# MCU_144_IOs.net
KiCad netlist of a schematic drawn in Altium Designer
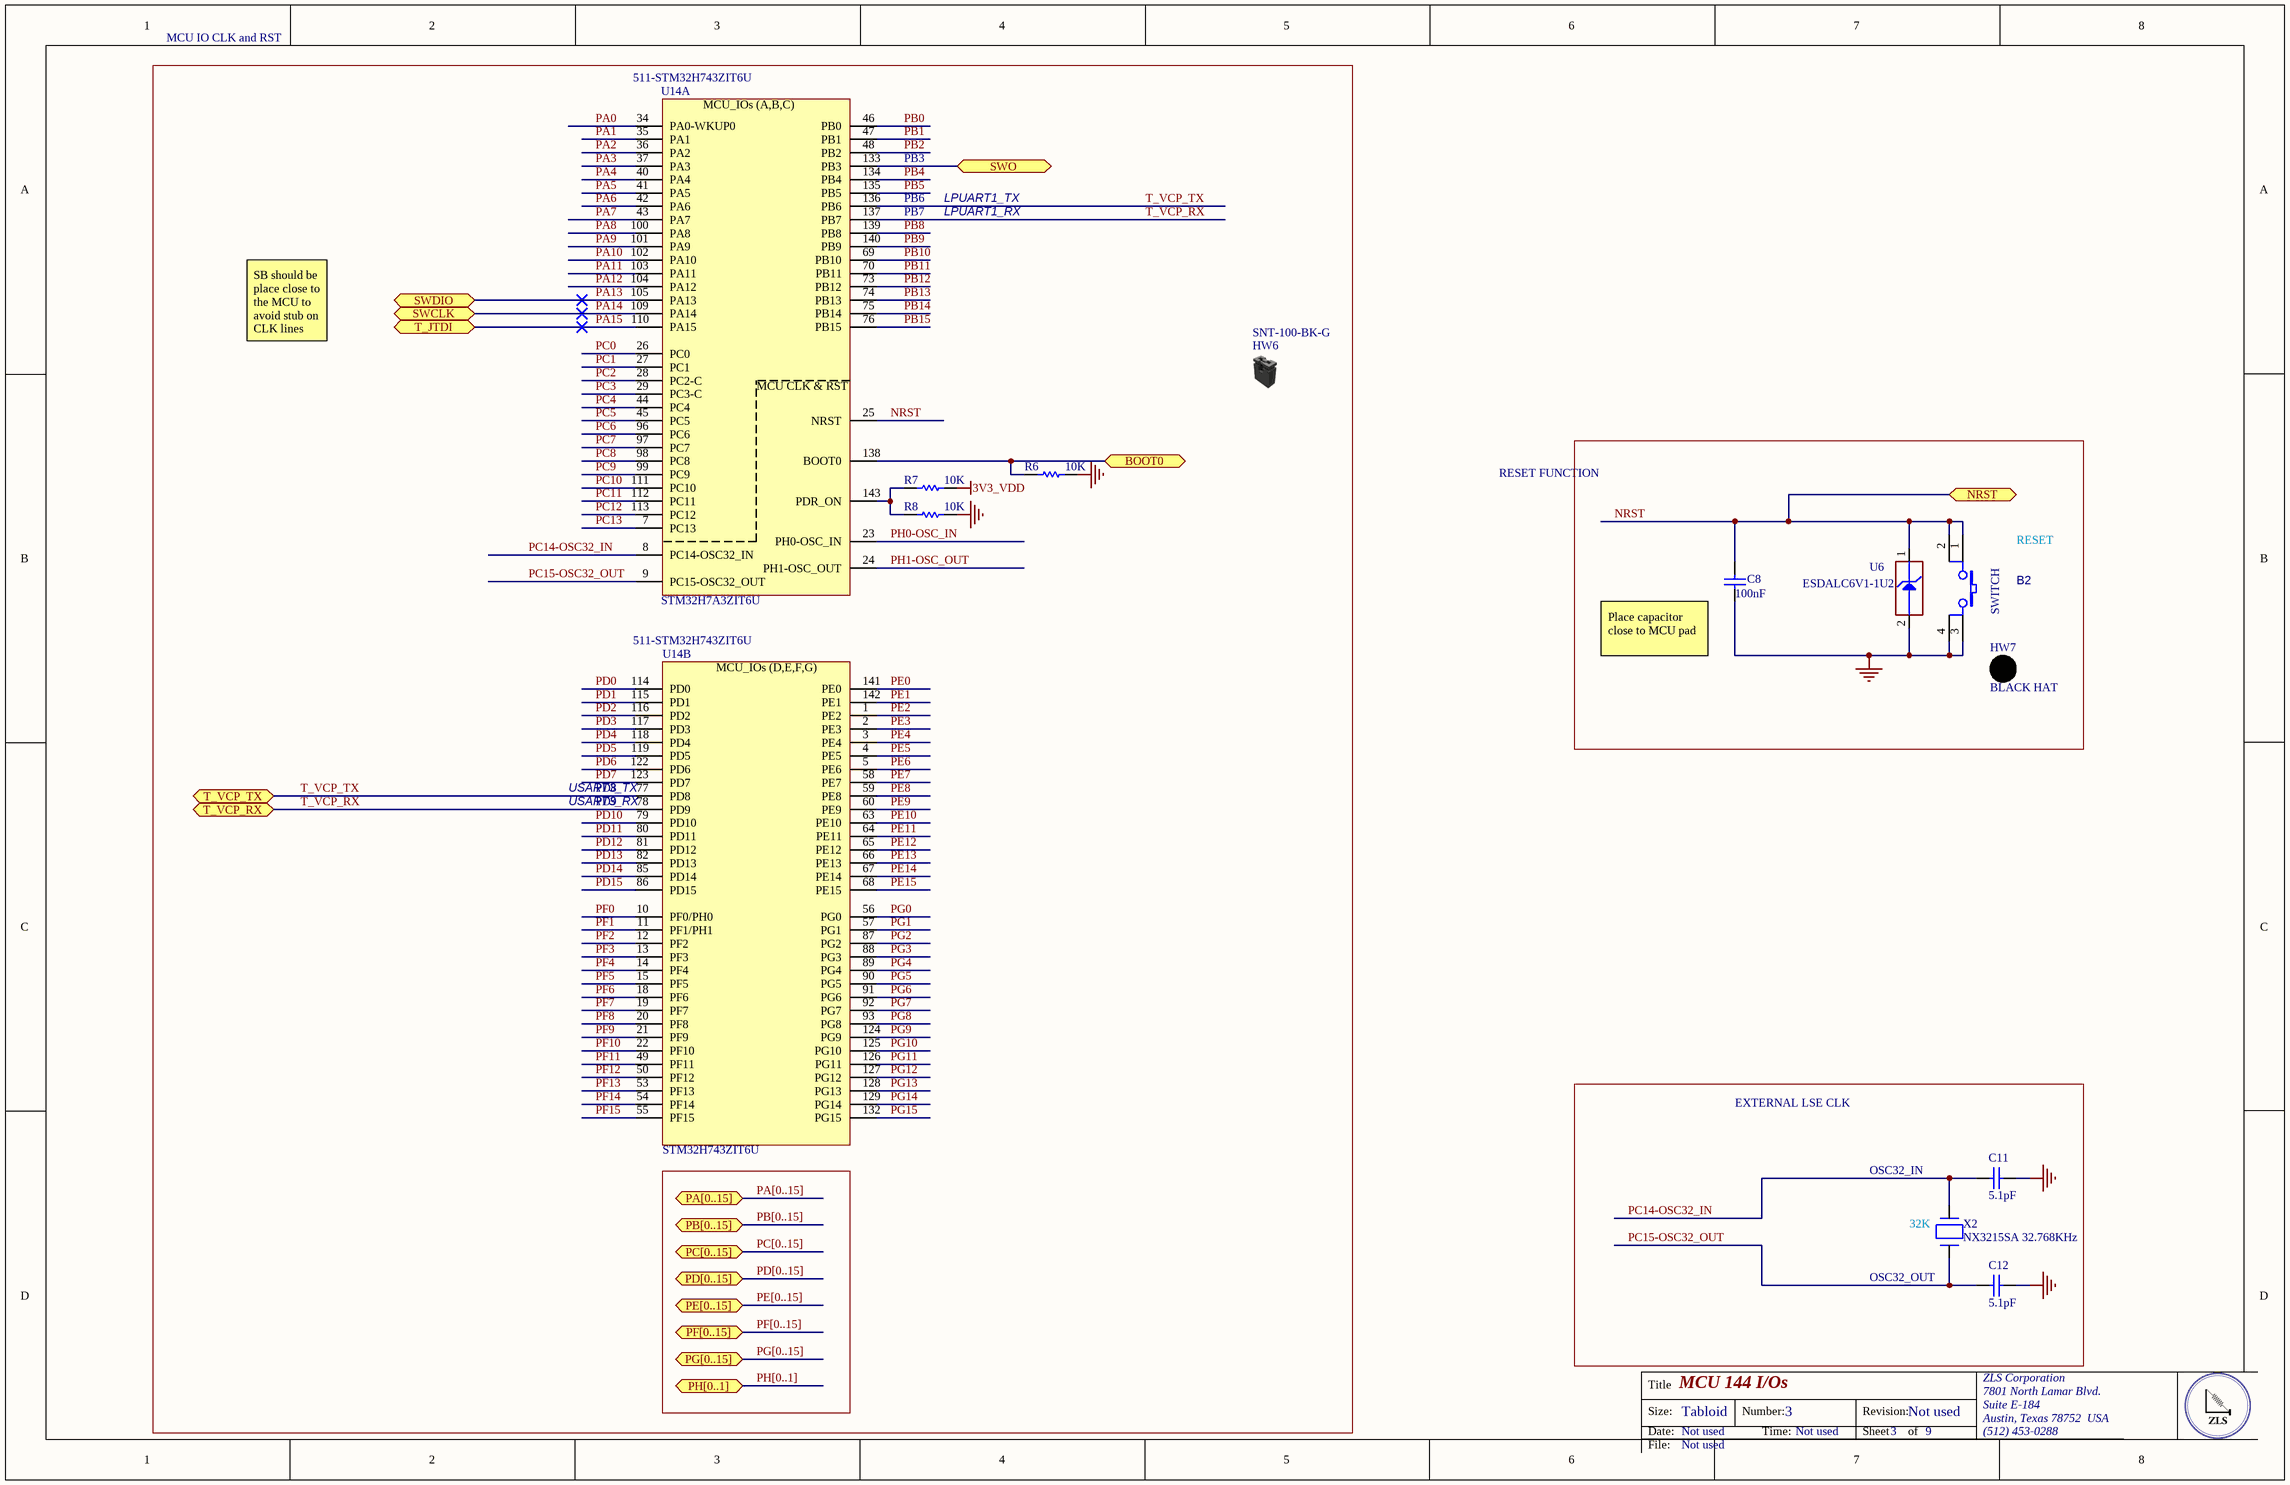
[diagram p0: MCU_144_IOs.SchDoc]

(export (version "E")
  (design (tool "Eeschema 10.0.6"))
  (components
    (comp (ref "B2")
      (value "SWITCH")
      (footprint "SWI_WEALTHMETAL_TD-0341_4P_BLACK")
      (description "Non-Open Push-Button 0.1A 24V BLACK")
      (fields
        (field (name "INTERNAL_PART_NUMBER") "MCD-00001")
        (field (name "MANUFACTURER_PART_NUMBER") "TD-0341")
        (field (name "PROVIDED_BY") "SUBCO")
      )
      (libsource (lib "MCD_PARTS_database") (part "SW-PUSH-CMS"))
    )
    (comp (ref "C8")
      (value "Capacitor")
      (footprint "C0402")
      (description "CAP CER 0.1UF 16V X7R 0402")
      (fields
        (field (name "MANUFACTURER") "Yageo")
        (field (name "MANUFACTURER PART NUMBER") "CC0402KRX7R7BB104")
        (field (name "CAPACITANCE") "100nF")
      )
      (libsource (lib "MCD_PARTS_database") (part "Capacitor"))
    )
    (comp (ref "C11")
      (value "5.1pF")
      (footprint "C0402")
      (description "Capacitor, MLCC, 5.1pF, 50V, NPO, +-0.25pF, 0402, T=0.5mm")
      (fields
        (field (name "INTERNAL_PART_NUMBER") "MCD-00003")
        (field (name "MANUFACTURER_PART_NUMBER") "CC0402CRNPO9BN5R1")
        (field (name "PROVIDED_BY") "SUBCO")
      )
      (libsource (lib "MCD_PARTS_database") (part "Capacitor"))
    )
    (comp (ref "C12")
      (value "5.1pF")
      (footprint "C0402")
      (description "Capacitor, MLCC, 5.1pF, 50V, NPO, +-0.25pF, 0402, T=0.5mm")
      (fields
        (field (name "INTERNAL_PART_NUMBER") "MCD-00003")
        (field (name "MANUFACTURER_PART_NUMBER") "CC0402CRNPO9BN5R1")
        (field (name "PROVIDED_BY") "SUBCO")
      )
      (libsource (lib "MCD_PARTS_database") (part "Capacitor"))
    )
    (comp (ref "HW6")
      (value "SNT-100-BK-G")
      (description "SHUNT 2.54mm BLACK")
      (fields
        (field (name "INTERNAL_PART_NUMBER") "MCD-00043")
        (field (name "MANUFACTURER") "SAMTEC")
        (field (name "PROVIDED_BY") "SUBCO")
      )
      (libsource (lib "MCD_PARTS_database") (part "Shunt Black 2.54mm"))
    )
    (comp (ref "HW7")
      (value "BLACK HAT")
      (description "Black Hat for switch TD0341X-G01-BLA")
      (fields
        (field (name "INTERNAL_PART_NUMBER") "MCD-00635")
        (field (name "MANUFACTURER_PART_NUMBER") "988.16.09.3.00003_SH-517")
        (field (name "PROVIDED_BY") "SUBCO")
      )
      (libsource (lib "MCD_PARTS_database") (part "BUTTON_HAT_BLACK"))
    )
    (comp (ref "R6")
      (value "10K")
      (footprint "R0603")
      (description "Resistor,10K,0603,1%,1/10W")
      (fields
        (field (name "INTERNAL_PART_NUMBER") "MCD-00220")
        (field (name "MANUFACTURER_PART_NUMBER") "RC0603FR-0710KL")
        (field (name "PROVIDED_BY") "SUBCO")
      )
      (libsource (lib "MCD_PARTS_database") (part "Resistor"))
    )
    (comp (ref "R7")
      (value "10K")
      (footprint "R0603")
      (description "Resistor,10K,0603,1%,1/10W")
      (fields
        (field (name "INTERNAL_PART_NUMBER") "MCD-00220")
        (field (name "MANUFACTURER_PART_NUMBER") "RC0603FR-0710KL")
        (field (name "PROVIDED_BY") "SUBCO")
      )
      (libsource (lib "MCD_PARTS_database") (part "Resistor"))
    )
    (comp (ref "R8")
      (value "10K")
      (footprint "R0603")
      (description "Resistor,10K,0603,1%,1/10W")
      (fields
        (field (name "INTERNAL_PART_NUMBER") "MCD-00220")
        (field (name "MANUFACTURER_PART_NUMBER") "RC0603FR-0710KL")
        (field (name "PROVIDED_BY") "SUBCO")
      )
      (libsource (lib "MCD_PARTS_database") (part "Resistor"))
    )
    (comp (ref "U6")
      (value "ESDALC6V1-1U2")
      (footprint "ESD_ST0201")
      (description "ESD protection 6V1")
      (fields
        (field (name "INTERNAL_PART_NUMBER") "MCD-00170")
        (field (name "MANUFACTURER") "STMICROELECTRONICS")
        (field (name "PROVIDED_BY") "SUBCO with ST control")
      )
      (libsource (lib "MCD_PARTS_database") (part "ESD-TRANSIL"))
    )
    (comp (ref "U14")
      (value "STM32H7A3ZIT6U")
      (footprint "ICC_LQFP144_20X20_P050_SOCKET_YAMAICHI_IC149-144-145-B5_NM")
      (description "STM32H7A3ZIT6U, LQFP144 package, 20x20")
      (fields
        (field (name "INTERNAL_PART_NUMBER") "MCD-01349")
        (field (name "MANUFACTURER") "STMICROELECTRONICS")
        (field (name "SUPPLIER PART NUMBER 1") "511-STM32H743ZIT6U")
        (field (name "PROVIDED_BY") "SUBCO with ST control")
      )
      (libsource (lib "MCD_PARTS_database") (part "STM32H7A3ZIT6"))
    )
    (comp (ref "X2")
      (value "NX3215SA 32.768KHz")
      (footprint "CRY_NX3215SA_2P")
      (description "Crystal 32.768kHz, 6pF, +-20ppm, 50Kohms max, SMD")
      (fields
        (field (name "INTERNAL_PART_NUMBER") "MCD-00091")
        (field (name "MANUFACTURER_PART_NUMBER") "NX3215SA 32.768KHz EXS00A-MU00525")
        (field (name "PROVIDED_BY") "SUBCO")
      )
      (libsource (lib "MCD_PARTS_database") (part "XTAL_2_PINS"))
    )
  )
  (nets
    (net (code "10") (name "/BOOT0") (class "Default")
      (node (ref "R6") (pin "1") (pinfunction "1_1") (pintype "passive"))
      (node (ref "U14") (pin "138") (pinfunction "BOOT0_138") (pintype "passive"))
    )
    (net (code "11") (name "/NRST") (class "Default")
      (node (ref "B2") (pin "1") (pinfunction "1_1") (pintype "passive"))
      (node (ref "B2") (pin "2") (pinfunction "2_2") (pintype "passive"))
      (node (ref "C8") (pin "2") (pinfunction "2_2") (pintype "passive"))
      (node (ref "U14") (pin "25") (pinfunction "NRST_25") (pintype "passive"))
      (node (ref "U6") (pin "1") (pinfunction "IO1_1") (pintype "passive"))
    )
    (net (code "12") (name "/PA0") (class "Default")
      (node (ref "U14") (pin "34") (pinfunction "PA0-WKUP0_34") (pintype "passive"))
    )
    (net (code "13") (name "/PA1") (class "Default")
      (node (ref "U14") (pin "35") (pinfunction "PA1_35") (pintype "passive"))
    )
    (net (code "14") (name "/PA2") (class "Default")
      (node (ref "U14") (pin "36") (pinfunction "PA2_36") (pintype "passive"))
    )
    (net (code "15") (name "/PA3") (class "Default")
      (node (ref "U14") (pin "37") (pinfunction "PA3_37") (pintype "passive"))
    )
    (net (code "16") (name "/PA4") (class "Default")
      (node (ref "U14") (pin "40") (pinfunction "PA4_40") (pintype "passive"))
    )
    (net (code "17") (name "/PA5") (class "Default")
      (node (ref "U14") (pin "41") (pinfunction "PA5_41") (pintype "passive"))
    )
    (net (code "18") (name "/PA6") (class "Default")
      (node (ref "U14") (pin "42") (pinfunction "PA6_42") (pintype "passive"))
    )
    (net (code "19") (name "/PA7") (class "Default")
      (node (ref "U14") (pin "43") (pinfunction "PA7_43") (pintype "passive"))
    )
    (net (code "20") (name "/PA8") (class "Default")
      (node (ref "U14") (pin "100") (pinfunction "PA8_100") (pintype "passive"))
    )
    (net (code "21") (name "/PA9") (class "Default")
      (node (ref "U14") (pin "101") (pinfunction "PA9_101") (pintype "passive"))
    )
    (net (code "22") (name "/PA10") (class "Default")
      (node (ref "U14") (pin "102") (pinfunction "PA10_102") (pintype "passive"))
    )
    (net (code "23") (name "/PA11") (class "Default")
      (node (ref "U14") (pin "103") (pinfunction "PA11_103") (pintype "passive"))
    )
    (net (code "24") (name "/PA12") (class "Default")
      (node (ref "U14") (pin "104") (pinfunction "PA12_104") (pintype "passive"))
    )
    (net (code "25") (name "/PA13") (class "Default")
      (node (ref "U14") (pin "105") (pinfunction "PA13_105") (pintype "passive"))
    )
    (net (code "26") (name "/PA14") (class "Default")
      (node (ref "U14") (pin "109") (pinfunction "PA14_109") (pintype "passive"))
    )
    (net (code "27") (name "/PA15") (class "Default")
      (node (ref "U14") (pin "110") (pinfunction "PA15_110") (pintype "passive"))
    )
    (net (code "29") (name "/PB0") (class "Default")
      (node (ref "U14") (pin "46") (pinfunction "PB0_46") (pintype "passive"))
    )
    (net (code "30") (name "/PB1") (class "Default")
      (node (ref "U14") (pin "47") (pinfunction "PB1_47") (pintype "passive"))
    )
    (net (code "31") (name "/PB2") (class "Default")
      (node (ref "U14") (pin "48") (pinfunction "PB2_48") (pintype "passive"))
    )
    (net (code "32") (name "/PB4") (class "Default")
      (node (ref "U14") (pin "134") (pinfunction "PB4_134") (pintype "passive"))
    )
    (net (code "33") (name "/PB5") (class "Default")
      (node (ref "U14") (pin "135") (pinfunction "PB5_135") (pintype "passive"))
    )
    (net (code "34") (name "/PB8") (class "Default")
      (node (ref "U14") (pin "139") (pinfunction "PB8_139") (pintype "passive"))
    )
    (net (code "35") (name "/PB9") (class "Default")
      (node (ref "U14") (pin "140") (pinfunction "PB9_140") (pintype "passive"))
    )
    (net (code "36") (name "/PB10") (class "Default")
      (node (ref "U14") (pin "69") (pinfunction "PB10_69") (pintype "passive"))
    )
    (net (code "37") (name "/PB11") (class "Default")
      (node (ref "U14") (pin "70") (pinfunction "PB11_70") (pintype "passive"))
    )
    (net (code "38") (name "/PB12") (class "Default")
      (node (ref "U14") (pin "73") (pinfunction "PB12_73") (pintype "passive"))
    )
    (net (code "39") (name "/PB13") (class "Default")
      (node (ref "U14") (pin "74") (pinfunction "PB13_74") (pintype "passive"))
    )
    (net (code "40") (name "/PB14") (class "Default")
      (node (ref "U14") (pin "75") (pinfunction "PB14_75") (pintype "passive"))
    )
    (net (code "41") (name "/PB15") (class "Default")
      (node (ref "U14") (pin "76") (pinfunction "PB15_76") (pintype "passive"))
    )
    (net (code "43") (name "/PC0") (class "Default")
      (node (ref "U14") (pin "26") (pinfunction "PC0_26") (pintype "passive"))
    )
    (net (code "44") (name "/PC1") (class "Default")
      (node (ref "U14") (pin "27") (pinfunction "PC1_27") (pintype "passive"))
    )
    (net (code "45") (name "/PC2") (class "Default")
      (node (ref "U14") (pin "28") (pinfunction "PC2-C_28") (pintype "passive"))
    )
    (net (code "46") (name "/PC3") (class "Default")
      (node (ref "U14") (pin "29") (pinfunction "PC3-C_29") (pintype "passive"))
    )
    (net (code "47") (name "/PC4") (class "Default")
      (node (ref "U14") (pin "44") (pinfunction "PC4_44") (pintype "passive"))
    )
    (net (code "48") (name "/PC5") (class "Default")
      (node (ref "U14") (pin "45") (pinfunction "PC5_45") (pintype "passive"))
    )
    (net (code "49") (name "/PC6") (class "Default")
      (node (ref "U14") (pin "96") (pinfunction "PC6_96") (pintype "passive"))
    )
    (net (code "50") (name "/PC7") (class "Default")
      (node (ref "U14") (pin "97") (pinfunction "PC7_97") (pintype "passive"))
    )
    (net (code "51") (name "/PC8") (class "Default")
      (node (ref "U14") (pin "98") (pinfunction "PC8_98") (pintype "passive"))
    )
    (net (code "52") (name "/PC9") (class "Default")
      (node (ref "U14") (pin "99") (pinfunction "PC9_99") (pintype "passive"))
    )
    (net (code "53") (name "/PC10") (class "Default")
      (node (ref "U14") (pin "111") (pinfunction "PC10_111") (pintype "passive"))
    )
    (net (code "54") (name "/PC11") (class "Default")
      (node (ref "U14") (pin "112") (pinfunction "PC11_112") (pintype "passive"))
    )
    (net (code "55") (name "/PC12") (class "Default")
      (node (ref "U14") (pin "113") (pinfunction "PC12_113") (pintype "passive"))
    )
    (net (code "56") (name "/PC13") (class "Default")
      (node (ref "U14") (pin "7") (pinfunction "PC13_7") (pintype "passive"))
    )
    (net (code "57") (name "/PC14-OSC32_IN") (class "Default")
      (node (ref "C11") (pin "1") (pinfunction "1_1") (pintype "passive"))
      (node (ref "U14") (pin "8") (pinfunction "PC14-OSC32_IN_8") (pintype "passive"))
      (node (ref "X2") (pin "2") (pinfunction "X2_2") (pintype "passive"))
    )
    (net (code "58") (name "/PC15-OSC32_OUT") (class "Default")
      (node (ref "C12") (pin "1") (pinfunction "1_1") (pintype "passive"))
      (node (ref "U14") (pin "9") (pinfunction "PC15-OSC32_OUT_9") (pintype "passive"))
      (node (ref "X2") (pin "1") (pinfunction "X1_1") (pintype "passive"))
    )
    (net (code "60") (name "/PD0") (class "Default")
      (node (ref "U14") (pin "114") (pinfunction "PD0_114") (pintype "passive"))
    )
    (net (code "61") (name "/PD1") (class "Default")
      (node (ref "U14") (pin "115") (pinfunction "PD1_115") (pintype "passive"))
    )
    (net (code "62") (name "/PD2") (class "Default")
      (node (ref "U14") (pin "116") (pinfunction "PD2_116") (pintype "passive"))
    )
    (net (code "63") (name "/PD3") (class "Default")
      (node (ref "U14") (pin "117") (pinfunction "PD3_117") (pintype "passive"))
    )
    (net (code "64") (name "/PD4") (class "Default")
      (node (ref "U14") (pin "118") (pinfunction "PD4_118") (pintype "passive"))
    )
    (net (code "65") (name "/PD5") (class "Default")
      (node (ref "U14") (pin "119") (pinfunction "PD5_119") (pintype "passive"))
    )
    (net (code "66") (name "/PD6") (class "Default")
      (node (ref "U14") (pin "122") (pinfunction "PD6_122") (pintype "passive"))
    )
    (net (code "67") (name "/PD7") (class "Default")
      (node (ref "U14") (pin "123") (pinfunction "PD7_123") (pintype "passive"))
    )
    (net (code "68") (name "/PD10") (class "Default")
      (node (ref "U14") (pin "79") (pinfunction "PD10_79") (pintype "passive"))
    )
    (net (code "69") (name "/PD11") (class "Default")
      (node (ref "U14") (pin "80") (pinfunction "PD11_80") (pintype "passive"))
    )
    (net (code "70") (name "/PD12") (class "Default")
      (node (ref "U14") (pin "81") (pinfunction "PD12_81") (pintype "passive"))
    )
    (net (code "71") (name "/PD13") (class "Default")
      (node (ref "U14") (pin "82") (pinfunction "PD13_82") (pintype "passive"))
    )
    (net (code "72") (name "/PD14") (class "Default")
      (node (ref "U14") (pin "85") (pinfunction "PD14_85") (pintype "passive"))
    )
    (net (code "73") (name "/PD15") (class "Default")
      (node (ref "U14") (pin "86") (pinfunction "PD15_86") (pintype "passive"))
    )
    (net (code "75") (name "/PE0") (class "Default")
      (node (ref "U14") (pin "141") (pinfunction "PE0_141") (pintype "passive"))
    )
    (net (code "76") (name "/PE1") (class "Default")
      (node (ref "U14") (pin "142") (pinfunction "PE1_142") (pintype "passive"))
    )
    (net (code "77") (name "/PE2") (class "Default")
      (node (ref "U14") (pin "1") (pinfunction "PE2_1") (pintype "passive"))
    )
    (net (code "78") (name "/PE3") (class "Default")
      (node (ref "U14") (pin "2") (pinfunction "PE3_2") (pintype "passive"))
    )
    (net (code "79") (name "/PE4") (class "Default")
      (node (ref "U14") (pin "3") (pinfunction "PE4_3") (pintype "passive"))
    )
    (net (code "80") (name "/PE5") (class "Default")
      (node (ref "U14") (pin "4") (pinfunction "PE5_4") (pintype "passive"))
    )
    (net (code "81") (name "/PE6") (class "Default")
      (node (ref "U14") (pin "5") (pinfunction "PE6_5") (pintype "passive"))
    )
    (net (code "82") (name "/PE7") (class "Default")
      (node (ref "U14") (pin "58") (pinfunction "PE7_58") (pintype "passive"))
    )
    (net (code "83") (name "/PE8") (class "Default")
      (node (ref "U14") (pin "59") (pinfunction "PE8_59") (pintype "passive"))
    )
    (net (code "84") (name "/PE9") (class "Default")
      (node (ref "U14") (pin "60") (pinfunction "PE9_60") (pintype "passive"))
    )
    (net (code "85") (name "/PE10") (class "Default")
      (node (ref "U14") (pin "63") (pinfunction "PE10_63") (pintype "passive"))
    )
    (net (code "86") (name "/PE11") (class "Default")
      (node (ref "U14") (pin "64") (pinfunction "PE11_64") (pintype "passive"))
    )
    (net (code "87") (name "/PE12") (class "Default")
      (node (ref "U14") (pin "65") (pinfunction "PE12_65") (pintype "passive"))
    )
    (net (code "88") (name "/PE13") (class "Default")
      (node (ref "U14") (pin "66") (pinfunction "PE13_66") (pintype "passive"))
    )
    (net (code "89") (name "/PE14") (class "Default")
      (node (ref "U14") (pin "67") (pinfunction "PE14_67") (pintype "passive"))
    )
    (net (code "90") (name "/PE15") (class "Default")
      (node (ref "U14") (pin "68") (pinfunction "PE15_68") (pintype "passive"))
    )
    (net (code "92") (name "/PF0") (class "Default")
      (node (ref "U14") (pin "10") (pinfunction "PF0/PH0_10") (pintype "passive"))
    )
    (net (code "93") (name "/PF1") (class "Default")
      (node (ref "U14") (pin "11") (pinfunction "PF1/PH1_11") (pintype "passive"))
    )
    (net (code "94") (name "/PF2") (class "Default")
      (node (ref "U14") (pin "12") (pinfunction "PF2_12") (pintype "passive"))
    )
    (net (code "95") (name "/PF3") (class "Default")
      (node (ref "U14") (pin "13") (pinfunction "PF3_13") (pintype "passive"))
    )
    (net (code "96") (name "/PF4") (class "Default")
      (node (ref "U14") (pin "14") (pinfunction "PF4_14") (pintype "passive"))
    )
    (net (code "97") (name "/PF5") (class "Default")
      (node (ref "U14") (pin "15") (pinfunction "PF5_15") (pintype "passive"))
    )
    (net (code "98") (name "/PF6") (class "Default")
      (node (ref "U14") (pin "18") (pinfunction "PF6_18") (pintype "passive"))
    )
    (net (code "99") (name "/PF7") (class "Default")
      (node (ref "U14") (pin "19") (pinfunction "PF7_19") (pintype "passive"))
    )
    (net (code "100") (name "/PF8") (class "Default")
      (node (ref "U14") (pin "20") (pinfunction "PF8_20") (pintype "passive"))
    )
    (net (code "101") (name "/PF9") (class "Default")
      (node (ref "U14") (pin "21") (pinfunction "PF9_21") (pintype "passive"))
    )
    (net (code "102") (name "/PF10") (class "Default")
      (node (ref "U14") (pin "22") (pinfunction "PF10_22") (pintype "passive"))
    )
    (net (code "103") (name "/PF11") (class "Default")
      (node (ref "U14") (pin "49") (pinfunction "PF11_49") (pintype "passive"))
    )
    (net (code "104") (name "/PF12") (class "Default")
      (node (ref "U14") (pin "50") (pinfunction "PF12_50") (pintype "passive"))
    )
    (net (code "105") (name "/PF13") (class "Default")
      (node (ref "U14") (pin "53") (pinfunction "PF13_53") (pintype "passive"))
    )
    (net (code "106") (name "/PF14") (class "Default")
      (node (ref "U14") (pin "54") (pinfunction "PF14_54") (pintype "passive"))
    )
    (net (code "107") (name "/PF15") (class "Default")
      (node (ref "U14") (pin "55") (pinfunction "PF15_55") (pintype "passive"))
    )
    (net (code "109") (name "/PG0") (class "Default")
      (node (ref "U14") (pin "56") (pinfunction "PG0_56") (pintype "passive"))
    )
    (net (code "110") (name "/PG1") (class "Default")
      (node (ref "U14") (pin "57") (pinfunction "PG1_57") (pintype "passive"))
    )
    (net (code "111") (name "/PG2") (class "Default")
      (node (ref "U14") (pin "87") (pinfunction "PG2_87") (pintype "passive"))
    )
    (net (code "112") (name "/PG3") (class "Default")
      (node (ref "U14") (pin "88") (pinfunction "PG3_88") (pintype "passive"))
    )
    (net (code "113") (name "/PG4") (class "Default")
      (node (ref "U14") (pin "89") (pinfunction "PG4_89") (pintype "passive"))
    )
    (net (code "114") (name "/PG5") (class "Default")
      (node (ref "U14") (pin "90") (pinfunction "PG5_90") (pintype "passive"))
    )
    (net (code "115") (name "/PG6") (class "Default")
      (node (ref "U14") (pin "91") (pinfunction "PG6_91") (pintype "passive"))
    )
    (net (code "116") (name "/PG7") (class "Default")
      (node (ref "U14") (pin "92") (pinfunction "PG7_92") (pintype "passive"))
    )
    (net (code "117") (name "/PG8") (class "Default")
      (node (ref "U14") (pin "93") (pinfunction "PG8_93") (pintype "passive"))
    )
    (net (code "118") (name "/PG9") (class "Default")
      (node (ref "U14") (pin "124") (pinfunction "PG9_124") (pintype "passive"))
    )
    (net (code "119") (name "/PG10") (class "Default")
      (node (ref "U14") (pin "125") (pinfunction "PG10_125") (pintype "passive"))
    )
    (net (code "120") (name "/PG11") (class "Default")
      (node (ref "U14") (pin "126") (pinfunction "PG11_126") (pintype "passive"))
    )
    (net (code "121") (name "/PG12") (class "Default")
      (node (ref "U14") (pin "127") (pinfunction "PG12_127") (pintype "passive"))
    )
    (net (code "122") (name "/PG13") (class "Default")
      (node (ref "U14") (pin "128") (pinfunction "PG13_128") (pintype "passive"))
    )
    (net (code "123") (name "/PG14") (class "Default")
      (node (ref "U14") (pin "129") (pinfunction "PG14_129") (pintype "passive"))
    )
    (net (code "124") (name "/PG15") (class "Default")
      (node (ref "U14") (pin "132") (pinfunction "PG15_132") (pintype "passive"))
    )
    (net (code "126") (name "/PH0-OSC_IN") (class "Default")
      (node (ref "U14") (pin "23") (pinfunction "PH0-OSC_IN_23") (pintype "passive"))
    )
    (net (code "127") (name "/PH1-OSC_OUT") (class "Default")
      (node (ref "U14") (pin "24") (pinfunction "PH1-OSC_OUT_24") (pintype "passive"))
    )
    (net (code "129") (name "/SWO") (class "Default")
      (node (ref "U14") (pin "133") (pinfunction "PB3_133") (pintype "passive"))
    )
    (net (code "130") (name "/T_VCP_RX") (class "Default")
      (node (ref "U14") (pin "137") (pinfunction "PB7_137") (pintype "passive"))
      (node (ref "U14") (pin "78") (pinfunction "PD9_78") (pintype "passive"))
    )
    (net (code "131") (name "/T_VCP_TX") (class "Default")
      (node (ref "U14") (pin "136") (pinfunction "PB6_136") (pintype "passive"))
      (node (ref "U14") (pin "77") (pinfunction "PD8_77") (pintype "passive"))
    )
    (net (code "132") (name "3V3_VDD") (class "Default")
      (node (ref "R7") (pin "2") (pinfunction "2_2") (pintype "passive"))
    )
    (net (code "133") (name "GND") (class "Default")
      (node (ref "B2") (pin "3") (pinfunction "3_3") (pintype "passive"))
      (node (ref "B2") (pin "4") (pinfunction "4_4") (pintype "passive"))
      (node (ref "C11") (pin "2") (pinfunction "2_2") (pintype "passive"))
      (node (ref "C12") (pin "2") (pinfunction "2_2") (pintype "passive"))
      (node (ref "C8") (pin "1") (pinfunction "1_1") (pintype "passive"))
      (node (ref "R6") (pin "2") (pinfunction "2_2") (pintype "passive"))
      (node (ref "R8") (pin "2") (pinfunction "2_2") (pintype "passive"))
      (node (ref "U6") (pin "2") (pinfunction "GND_2") (pintype "passive"))
    )
    (net (code "134") (name "Net-(U14A-PDR_ON)") (class "Default")
      (node (ref "R7") (pin "1") (pinfunction "1_1") (pintype "passive"))
      (node (ref "R8") (pin "1") (pinfunction "1_1") (pintype "passive"))
      (node (ref "U14") (pin "143") (pinfunction "PDR_ON_143") (pintype "passive"))
    )
  )
)
